# motor-driver-VNH23P30_TH.net
KiCad netlist of a schematic drawn in EAGLE
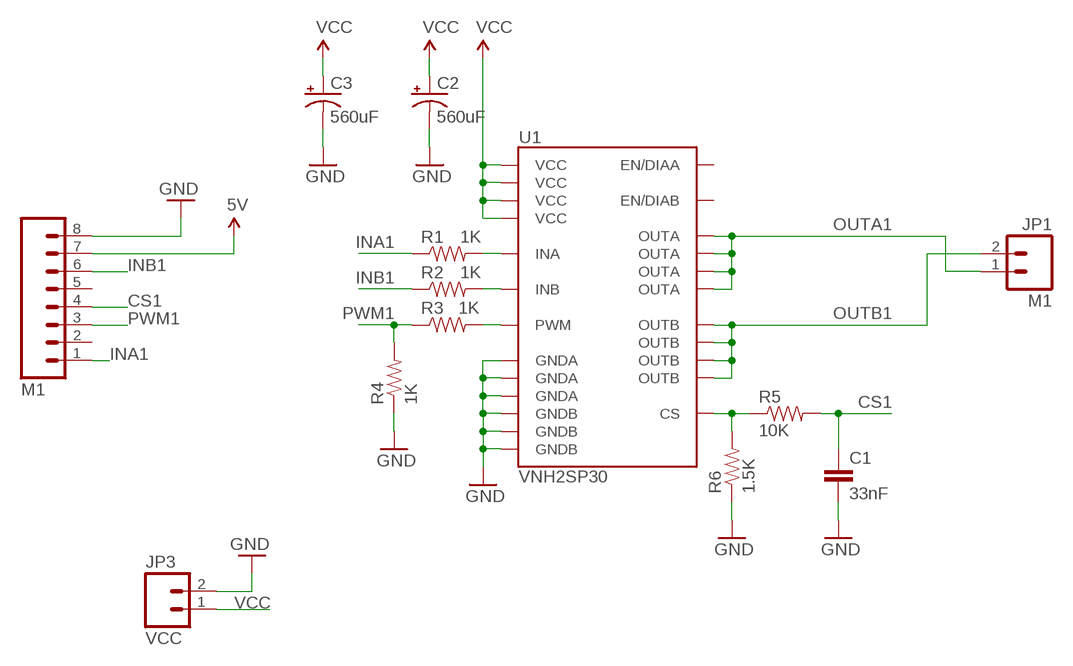
[diagram p0: schematic, sheet 1]

(export (version "E")
  (design (tool "Eeschema 10.0.6"))
  (components
    (comp (ref "C1")
      (value "33nF")
      (footprint "eagle-import:CAP-PTH-SMALLEZ")
      (libsource (lib "eagle-import") (part "CAPEZ"))
    )
    (comp (ref "C2")
      (value "560uF")
      (footprint "eagle-import:CPOL-RADIAL-1000UF-25V")
      (libsource (lib "eagle-import") (part "CAP_POLPTH4"))
    )
    (comp (ref "C3")
      (value "560uF")
      (footprint "eagle-import:CPOL-RADIAL-1000UF-25V")
      (libsource (lib "eagle-import") (part "CAP_POLPTH4"))
    )
    (comp (ref "JP1")
      (value "M1")
      (footprint "eagle-import:1X02_XTRA_BIG")
      (libsource (lib "eagle-import") (part "M02PTH4"))
    )
    (comp (ref "JP3")
      (value "VCC")
      (footprint "eagle-import:1X02_XTRA_BIG")
      (libsource (lib "eagle-import") (part "M02PTH4"))
    )
    (comp (ref "P")
      (value "M1")
      (footprint "eagle-import:1X08")
      (libsource (lib "eagle-import") (part "M081X08"))
    )
    (comp (ref "R1")
      (value "1K")
      (footprint "eagle-import:1_6W-RES")
      (libsource (lib "eagle-import") (part "RESISTORPTH-1/6W"))
    )
    (comp (ref "R2")
      (value "1K")
      (footprint "eagle-import:1_6W-RES")
      (libsource (lib "eagle-import") (part "RESISTORPTH-1/6W"))
    )
    (comp (ref "R3")
      (value "1K")
      (footprint "eagle-import:1_6W-RES")
      (libsource (lib "eagle-import") (part "RESISTORPTH-1/6W"))
    )
    (comp (ref "R4")
      (value "1K")
      (footprint "eagle-import:1_6W-RES")
      (libsource (lib "eagle-import") (part "RESISTORPTH-1/6W"))
    )
    (comp (ref "R5")
      (value "10K")
      (footprint "eagle-import:1_6W-RES")
      (libsource (lib "eagle-import") (part "RESISTORPTH-1/6W"))
    )
    (comp (ref "R6")
      (value "1.5K")
      (footprint "eagle-import:1_6W-RES")
      (libsource (lib "eagle-import") (part "RESISTORPTH-1/6W"))
    )
    (comp (ref "U1")
      (value "VNH2SP30")
      (footprint "eagle-import:VNH2SP30")
      (libsource (lib "eagle-import") (part "VNH2SP30"))
    )
  )
  (nets
    (net (code "1") (name "/CS1") (class "Default")
      (node (ref "C1") (pin "1") (pinfunction "1_1") (pintype "passive"))
      (node (ref "P") (pin "4") (pinfunction "4_4") (pintype "passive"))
      (node (ref "R5") (pin "2") (pinfunction "2_2") (pintype "passive"))
    )
    (net (code "2") (name "/INA1") (class "Default")
      (node (ref "P") (pin "1") (pinfunction "1_1") (pintype "passive"))
      (node (ref "R1") (pin "1") (pinfunction "1_1") (pintype "passive"))
    )
    (net (code "3") (name "/INB1") (class "Default")
      (node (ref "P") (pin "6") (pinfunction "6_6") (pintype "passive"))
      (node (ref "R2") (pin "1") (pinfunction "1_1") (pintype "passive"))
    )
    (net (code "4") (name "/OUTA1") (class "Default")
      (node (ref "JP1") (pin "1") (pinfunction "1_1") (pintype "passive"))
      (node (ref "U1") (pin "1") (pinfunction "OUTA_1") (pintype "bidirectional"))
      (node (ref "U1") (pin "25") (pinfunction "OUTA_25") (pintype "bidirectional"))
      (node (ref "U1") (pin "30") (pinfunction "OUTA_30") (pintype "bidirectional"))
      (node (ref "U1") (pin "SLUG3") (pinfunction "OUTA_SLUG3") (pintype "bidirectional"))
    )
    (net (code "5") (name "/OUTB1") (class "Default")
      (node (ref "JP1") (pin "2") (pinfunction "2_2") (pintype "passive"))
      (node (ref "U1") (pin "15") (pinfunction "OUTB_15") (pintype "bidirectional"))
      (node (ref "U1") (pin "16") (pinfunction "OUTB_16") (pintype "bidirectional"))
      (node (ref "U1") (pin "21") (pinfunction "OUTB_21") (pintype "bidirectional"))
      (node (ref "U1") (pin "SLUG2") (pinfunction "OUTB_SLUG2") (pintype "bidirectional"))
    )
    (net (code "6") (name "/PWM1") (class "Default")
      (node (ref "P") (pin "3") (pinfunction "3_3") (pintype "passive"))
      (node (ref "R3") (pin "1") (pinfunction "1_1") (pintype "passive"))
      (node (ref "R4") (pin "2") (pinfunction "2_2") (pintype "passive"))
    )
    (net (code "7") (name "5V") (class "Default")
      (node (ref "P") (pin "7") (pinfunction "7_7") (pintype "passive"))
    )
    (net (code "8") (name "GND") (class "Default")
      (node (ref "C1") (pin "2") (pinfunction "2_2") (pintype "passive"))
      (node (ref "C2") (pin "2") (pinfunction "-_2") (pintype "passive"))
      (node (ref "C3") (pin "2") (pinfunction "-_2") (pintype "passive"))
      (node (ref "JP3") (pin "2") (pinfunction "2_2") (pintype "passive"))
      (node (ref "P") (pin "8") (pinfunction "8_8") (pintype "passive"))
      (node (ref "R4") (pin "1") (pinfunction "1_1") (pintype "passive"))
      (node (ref "R6") (pin "1") (pinfunction "1_1") (pintype "passive"))
      (node (ref "U1") (pin "18") (pinfunction "GNDB_18") (pintype "bidirectional"))
      (node (ref "U1") (pin "19") (pinfunction "GNDB_19") (pintype "bidirectional"))
      (node (ref "U1") (pin "20") (pinfunction "GNDB_20") (pintype "bidirectional"))
      (node (ref "U1") (pin "26") (pinfunction "GNDA_26") (pintype "bidirectional"))
      (node (ref "U1") (pin "27") (pinfunction "GNDA_27") (pintype "bidirectional"))
      (node (ref "U1") (pin "28") (pinfunction "GNDA_28") (pintype "bidirectional"))
    )
    (net (code "9") (name "Net-(U1-CS)") (class "Default")
      (node (ref "R5") (pin "1") (pinfunction "1_1") (pintype "passive"))
      (node (ref "R6") (pin "2") (pinfunction "2_2") (pintype "passive"))
      (node (ref "U1") (pin "9") (pinfunction "CS_9") (pintype "bidirectional"))
    )
    (net (code "10") (name "Net-(U1-INA)") (class "Default")
      (node (ref "R1") (pin "2") (pinfunction "2_2") (pintype "passive"))
      (node (ref "U1") (pin "5") (pinfunction "INA_5") (pintype "bidirectional"))
    )
    (net (code "11") (name "Net-(U1-INB)") (class "Default")
      (node (ref "R2") (pin "2") (pinfunction "2_2") (pintype "passive"))
      (node (ref "U1") (pin "11") (pinfunction "INB_11") (pintype "bidirectional"))
    )
    (net (code "12") (name "Net-(U1-PWM)") (class "Default")
      (node (ref "R3") (pin "2") (pinfunction "2_2") (pintype "passive"))
      (node (ref "U1") (pin "8") (pinfunction "PWM_8") (pintype "bidirectional"))
    )
    (net (code "13") (name "VCC") (class "Default")
      (node (ref "C2") (pin "1") (pinfunction "+_1") (pintype "passive"))
      (node (ref "C3") (pin "1") (pinfunction "+_1") (pintype "passive"))
      (node (ref "JP3") (pin "1") (pinfunction "1_1") (pintype "passive"))
      (node (ref "U1") (pin "13") (pinfunction "VCC_13") (pintype "bidirectional"))
      (node (ref "U1") (pin "23") (pinfunction "VCC_23") (pintype "bidirectional"))
      (node (ref "U1") (pin "3") (pinfunction "VCC_3") (pintype "bidirectional"))
      (node (ref "U1") (pin "SLUG1") (pinfunction "VCC_SLUG1") (pintype "bidirectional"))
    )
    (net (code "14") (name "unconnected-(P-Pad2)") (class "Default")
      (node (ref "P") (pin "2") (pinfunction "2_2") (pintype "passive"))
    )
    (net (code "15") (name "unconnected-(P-Pad5)") (class "Default")
      (node (ref "P") (pin "5") (pinfunction "5_5") (pintype "passive"))
    )
    (net (code "16") (name "unconnected-(U1-EN{slash}DIAA-Pad6)") (class "Default")
      (node (ref "U1") (pin "6") (pinfunction "EN/DIAA_6") (pintype "bidirectional"))
    )
    (net (code "17") (name "unconnected-(U1-EN{slash}DIAB-Pad10)") (class "Default")
      (node (ref "U1") (pin "10") (pinfunction "EN/DIAB_10") (pintype "bidirectional"))
    )
  )
)
